# Stroomtrekker.net
KiCad netlist of a schematic drawn in EAGLE
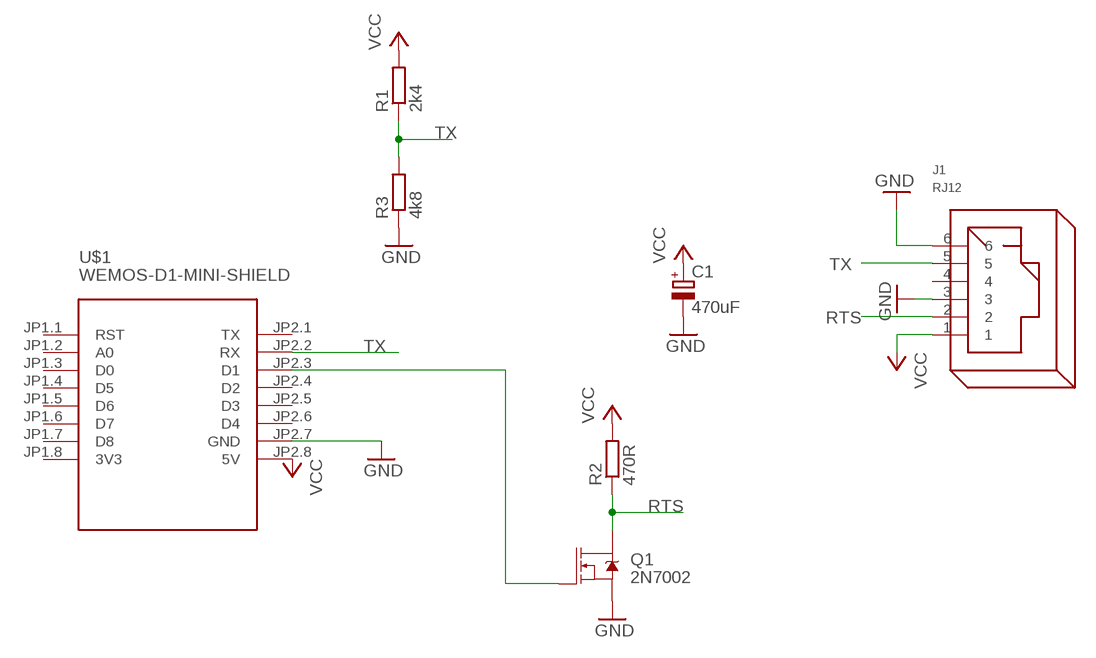
[diagram p0: schematic, sheet 1]

(export (version "E")
  (design (tool "Eeschema 10.0.6"))
  (components
    (comp (ref "C1")
      (value "470uF")
      (footprint "eagle-import:E2,5-6")
      (libsource (lib "eagle-import") (part "CPOL-EUE2.5-6"))
    )
    (comp (ref "J1")
      (value "RJ12")
      (footprint "eagle-import:RJ12")
      (libsource (lib "eagle-import") (part "RJ12"))
    )
    (comp (ref "Q1")
      (value "2N7002")
      (footprint "eagle-import:SOT323")
      (libsource (lib "eagle-import") (part "MOSFET-NCH-2N7002PW"))
    )
    (comp (ref "R1")
      (value "2k4")
      (footprint "eagle-import:R0805")
      (libsource (lib "eagle-import") (part "R-EU_R0805"))
    )
    (comp (ref "R2")
      (value "470R")
      (footprint "eagle-import:R0805")
      (libsource (lib "eagle-import") (part "R-EU_R0805"))
    )
    (comp (ref "R3")
      (value "4k8")
      (footprint "eagle-import:R0805")
      (libsource (lib "eagle-import") (part "R-EU_R0805"))
    )
    (comp (ref "U$1")
      (value "WEMOS-D1-MINI-SHIELD")
      (footprint "eagle-import:WEMOS-D1-MINI-SHIELD")
      (libsource (lib "eagle-import") (part "WEMOS-D1-MINI-SHIELD"))
    )
  )
  (nets
    (net (code "1") (name "/3V3") (class "Default")
      (node (ref "U$1") (pin "JP1.8") (pinfunction "3V3_JP1.8") (pintype "power_in"))
    )
    (net (code "2") (name "/RTS") (class "Default")
      (node (ref "J1") (pin "2") (pinfunction "2_2") (pintype "bidirectional"))
      (node (ref "Q1") (pin "3") (pinfunction "D_3") (pintype "bidirectional"))
      (node (ref "R2") (pin "1") (pinfunction "1_1") (pintype "passive"))
    )
    (net (code "3") (name "/TX") (class "Default")
      (node (ref "J1") (pin "5") (pinfunction "5_5") (pintype "bidirectional"))
      (node (ref "R1") (pin "1") (pinfunction "1_1") (pintype "passive"))
      (node (ref "R3") (pin "2") (pinfunction "2_2") (pintype "passive"))
      (node (ref "U$1") (pin "JP2.2") (pinfunction "RX_JP2.2") (pintype "bidirectional"))
    )
    (net (code "4") (name "GND") (class "Default")
      (node (ref "C1") (pin "-") (pinfunction "-_-") (pintype "passive"))
      (node (ref "J1") (pin "3") (pinfunction "3_3") (pintype "bidirectional"))
      (node (ref "J1") (pin "6") (pinfunction "6_6") (pintype "bidirectional"))
      (node (ref "Q1") (pin "2") (pinfunction "S_2") (pintype "bidirectional"))
      (node (ref "R3") (pin "1") (pinfunction "1_1") (pintype "passive"))
      (node (ref "U$1") (pin "JP2.7") (pinfunction "GND_JP2.7") (pintype "power_in"))
    )
    (net (code "5") (name "Net-(Q1-G)") (class "Default")
      (node (ref "Q1") (pin "1") (pinfunction "G_1") (pintype "bidirectional"))
      (node (ref "U$1") (pin "JP2.3") (pinfunction "D1_JP2.3") (pintype "bidirectional"))
    )
    (net (code "6") (name "VCC") (class "Default")
      (node (ref "C1") (pin "+") (pinfunction "+_+") (pintype "passive"))
      (node (ref "J1") (pin "1") (pinfunction "1_1") (pintype "bidirectional"))
      (node (ref "R1") (pin "2") (pinfunction "2_2") (pintype "passive"))
      (node (ref "R2") (pin "2") (pinfunction "2_2") (pintype "passive"))
      (node (ref "U$1") (pin "JP2.8") (pinfunction "5V_JP2.8") (pintype "power_in"))
    )
    (net (code "7") (name "unconnected-(J1-Pad4)") (class "Default")
      (node (ref "J1") (pin "4") (pinfunction "4_4") (pintype "bidirectional"))
    )
    (net (code "8") (name "unconnected-(U$1-A0-PadJP1.2)") (class "Default")
      (node (ref "U$1") (pin "JP1.2") (pinfunction "A0_JP1.2") (pintype "bidirectional"))
    )
    (net (code "9") (name "unconnected-(U$1-D0-PadJP1.3)") (class "Default")
      (node (ref "U$1") (pin "JP1.3") (pinfunction "D0_JP1.3") (pintype "bidirectional"))
    )
    (net (code "10") (name "unconnected-(U$1-D2-PadJP2.4)") (class "Default")
      (node (ref "U$1") (pin "JP2.4") (pinfunction "D2_JP2.4") (pintype "bidirectional"))
    )
    (net (code "11") (name "unconnected-(U$1-D3-PadJP2.5)") (class "Default")
      (node (ref "U$1") (pin "JP2.5") (pinfunction "D3_JP2.5") (pintype "bidirectional"))
    )
    (net (code "12") (name "unconnected-(U$1-D4-PadJP2.6)") (class "Default")
      (node (ref "U$1") (pin "JP2.6") (pinfunction "D4_JP2.6") (pintype "bidirectional"))
    )
    (net (code "13") (name "unconnected-(U$1-D5-PadJP1.4)") (class "Default")
      (node (ref "U$1") (pin "JP1.4") (pinfunction "D5_JP1.4") (pintype "bidirectional"))
    )
    (net (code "14") (name "unconnected-(U$1-D6-PadJP1.5)") (class "Default")
      (node (ref "U$1") (pin "JP1.5") (pinfunction "D6_JP1.5") (pintype "bidirectional"))
    )
    (net (code "15") (name "unconnected-(U$1-D7-PadJP1.6)") (class "Default")
      (node (ref "U$1") (pin "JP1.6") (pinfunction "D7_JP1.6") (pintype "bidirectional"))
    )
    (net (code "16") (name "unconnected-(U$1-D8-PadJP1.7)") (class "Default")
      (node (ref "U$1") (pin "JP1.7") (pinfunction "D8_JP1.7") (pintype "bidirectional"))
    )
    (net (code "17") (name "unconnected-(U$1-RST-PadJP1.1)") (class "Default")
      (node (ref "U$1") (pin "JP1.1") (pinfunction "RST_JP1.1") (pintype "bidirectional"))
    )
    (net (code "18") (name "unconnected-(U$1-TX-PadJP2.1)") (class "Default")
      (node (ref "U$1") (pin "JP2.1") (pinfunction "TX_JP2.1") (pintype "bidirectional"))
    )
  )
)
